# ADS7952-Q1.net
KiCad netlist of a schematic drawn in Altium Designer
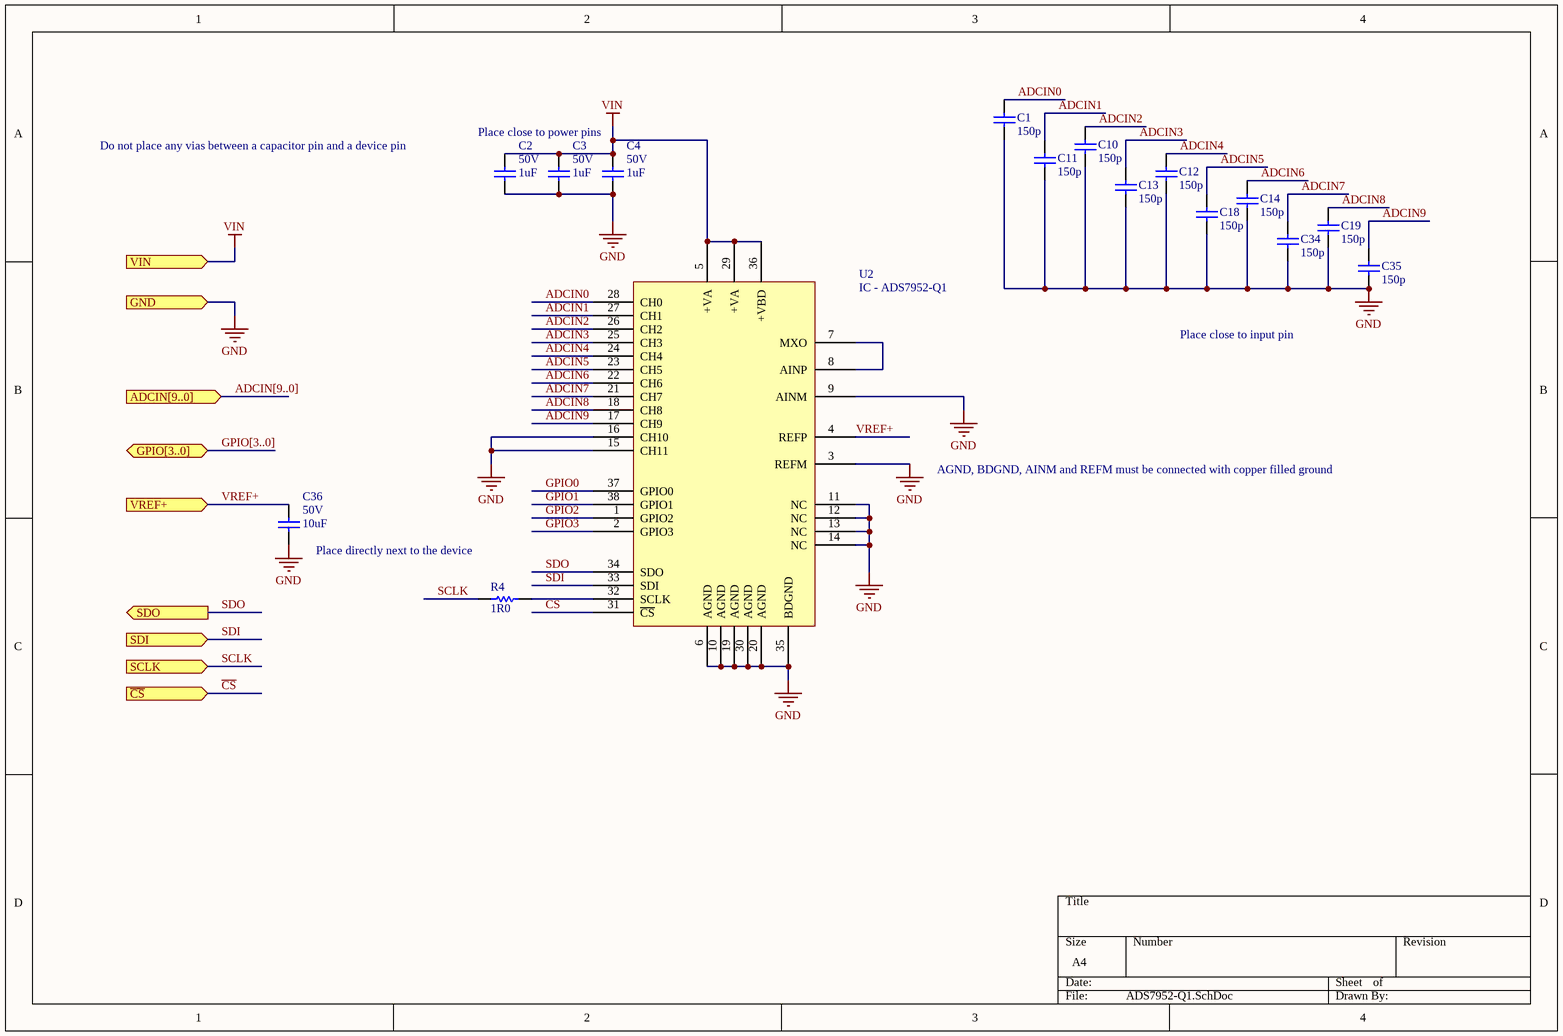
[diagram p0: ADS7952-Q1.SchDoc]

(export (version "E")
  (design (tool "Eeschema 10.0.6"))
  (components
    (comp (ref "C1")
      (value "150p")
      (footprint "CS-0603")
      (fields
        (field (name "TOLERANCE") "10%")
        (field (name "VOLTAGE") "16V")
        (field (name "Comment") "CS - CAPACITOR")
      )
      (libsource (lib "CHINOOK_LIBRARY") (part "CS - CAPACITOR"))
    )
    (comp (ref "C2")
      (value "1uF")
      (footprint "CS-0603")
      (fields
        (field (name "TOLERANCE") "10%")
        (field (name "VOLTAGE") "50V")
        (field (name "Comment") "CS - CAPACITOR")
      )
      (libsource (lib "CHINOOK_LIBRARY") (part "CS - CAPACITOR"))
    )
    (comp (ref "C3")
      (value "1uF")
      (footprint "CS-0603")
      (fields
        (field (name "TOLERANCE") "10%")
        (field (name "VOLTAGE") "50V")
        (field (name "Comment") "CS - CAPACITOR")
      )
      (libsource (lib "CHINOOK_LIBRARY") (part "CS - CAPACITOR"))
    )
    (comp (ref "C4")
      (value "1uF")
      (footprint "CS-0603")
      (fields
        (field (name "TOLERANCE") "10%")
        (field (name "VOLTAGE") "50V")
        (field (name "Comment") "CS - CAPACITOR")
      )
      (libsource (lib "CHINOOK_LIBRARY") (part "CS - CAPACITOR"))
    )
    (comp (ref "C10")
      (value "150p")
      (footprint "CS-0603")
      (fields
        (field (name "TOLERANCE") "10%")
        (field (name "VOLTAGE") "16V")
        (field (name "Comment") "CS - CAPACITOR")
      )
      (libsource (lib "CHINOOK_LIBRARY") (part "CS - CAPACITOR"))
    )
    (comp (ref "C11")
      (value "150p")
      (footprint "CS-0603")
      (fields
        (field (name "TOLERANCE") "10%")
        (field (name "VOLTAGE") "16V")
        (field (name "Comment") "CS - CAPACITOR")
      )
      (libsource (lib "CHINOOK_LIBRARY") (part "CS - CAPACITOR"))
    )
    (comp (ref "C12")
      (value "150p")
      (footprint "CS-0603")
      (fields
        (field (name "TOLERANCE") "10%")
        (field (name "VOLTAGE") "16V")
        (field (name "Comment") "CS - CAPACITOR")
      )
      (libsource (lib "CHINOOK_LIBRARY") (part "CS - CAPACITOR"))
    )
    (comp (ref "C13")
      (value "150p")
      (footprint "CS-0603")
      (fields
        (field (name "TOLERANCE") "10%")
        (field (name "VOLTAGE") "16V")
        (field (name "Comment") "CS - CAPACITOR")
      )
      (libsource (lib "CHINOOK_LIBRARY") (part "CS - CAPACITOR"))
    )
    (comp (ref "C14")
      (value "150p")
      (footprint "CS-0603")
      (fields
        (field (name "TOLERANCE") "10%")
        (field (name "VOLTAGE") "16V")
        (field (name "Comment") "CS - CAPACITOR")
      )
      (libsource (lib "CHINOOK_LIBRARY") (part "CS - CAPACITOR"))
    )
    (comp (ref "C18")
      (value "150p")
      (footprint "CS-0603")
      (fields
        (field (name "TOLERANCE") "10%")
        (field (name "VOLTAGE") "16V")
        (field (name "Comment") "CS - CAPACITOR")
      )
      (libsource (lib "CHINOOK_LIBRARY") (part "CS - CAPACITOR"))
    )
    (comp (ref "C19")
      (value "150p")
      (footprint "CS-0603")
      (fields
        (field (name "TOLERANCE") "10%")
        (field (name "VOLTAGE") "16V")
        (field (name "Comment") "CS - CAPACITOR")
      )
      (libsource (lib "CHINOOK_LIBRARY") (part "CS - CAPACITOR"))
    )
    (comp (ref "C34")
      (value "150p")
      (footprint "CS-0603")
      (fields
        (field (name "TOLERANCE") "10%")
        (field (name "VOLTAGE") "16V")
        (field (name "Comment") "CS - CAPACITOR")
      )
      (libsource (lib "CHINOOK_LIBRARY") (part "CS - CAPACITOR"))
    )
    (comp (ref "C35")
      (value "150p")
      (footprint "CS-0603")
      (fields
        (field (name "TOLERANCE") "10%")
        (field (name "VOLTAGE") "16V")
        (field (name "Comment") "CS - CAPACITOR")
      )
      (libsource (lib "CHINOOK_LIBRARY") (part "CS - CAPACITOR"))
    )
    (comp (ref "C36")
      (value "10uF")
      (footprint "CS-0603")
      (fields
        (field (name "TOLERANCE") "10%")
        (field (name "VOLTAGE") "50V")
        (field (name "Comment") "CS - CAPACITOR")
      )
      (libsource (lib "CHINOOK_LIBRARY") (part "CS - CAPACITOR"))
    )
    (comp (ref "R4")
      (value "1R0")
      (footprint "RS-0603")
      (fields
        (field (name "TOLERANCE") "RES TOL")
        (field (name "POWER") "RES POWER")
        (field (name "Comment") "RS - RESISTOR")
      )
      (libsource (lib "CHINOOK_LIBRARY") (part "RS - RESISTOR"))
    )
    (comp (ref "U2")
      (value "IC - ADS7952-Q1")
      (footprint "IC-TSSOP-38")
      (description "ADC 12 bits 12 channels MUX SPI")
      (libsource (lib "CHINOOK_LIBRARY") (part "IC - ADS7952-Q1"))
    )
  )
  (nets
    (net (code "1") (name "/ADCIN0") (class "Default")
      (node (ref "C1") (pin "2") (pinfunction "2_2") (pintype "passive"))
      (node (ref "U2") (pin "28") (pinfunction "CH0_28") (pintype "passive"))
    )
    (net (code "2") (name "/ADCIN1") (class "Default")
      (node (ref "C11") (pin "2") (pinfunction "2_2") (pintype "passive"))
      (node (ref "U2") (pin "27") (pinfunction "CH1_27") (pintype "passive"))
    )
    (net (code "3") (name "/ADCIN2") (class "Default")
      (node (ref "C10") (pin "2") (pinfunction "2_2") (pintype "passive"))
      (node (ref "U2") (pin "26") (pinfunction "CH2_26") (pintype "passive"))
    )
    (net (code "4") (name "/ADCIN3") (class "Default")
      (node (ref "C13") (pin "2") (pinfunction "2_2") (pintype "passive"))
      (node (ref "U2") (pin "25") (pinfunction "CH3_25") (pintype "passive"))
    )
    (net (code "5") (name "/ADCIN4") (class "Default")
      (node (ref "C12") (pin "2") (pinfunction "2_2") (pintype "passive"))
      (node (ref "U2") (pin "24") (pinfunction "CH4_24") (pintype "passive"))
    )
    (net (code "6") (name "/ADCIN5") (class "Default")
      (node (ref "C18") (pin "2") (pinfunction "2_2") (pintype "passive"))
      (node (ref "U2") (pin "23") (pinfunction "CH5_23") (pintype "passive"))
    )
    (net (code "7") (name "/ADCIN6") (class "Default")
      (node (ref "C14") (pin "2") (pinfunction "2_2") (pintype "passive"))
      (node (ref "U2") (pin "22") (pinfunction "CH6_22") (pintype "passive"))
    )
    (net (code "8") (name "/ADCIN7") (class "Default")
      (node (ref "C34") (pin "2") (pinfunction "2_2") (pintype "passive"))
      (node (ref "U2") (pin "21") (pinfunction "CH7_21") (pintype "passive"))
    )
    (net (code "9") (name "/ADCIN8") (class "Default")
      (node (ref "C19") (pin "2") (pinfunction "2_2") (pintype "passive"))
      (node (ref "U2") (pin "18") (pinfunction "CH8_18") (pintype "passive"))
    )
    (net (code "10") (name "/ADCIN9") (class "Default")
      (node (ref "C35") (pin "2") (pinfunction "2_2") (pintype "passive"))
      (node (ref "U2") (pin "17") (pinfunction "CH9_17") (pintype "passive"))
    )
    (net (code "12") (name "/GPIO0") (class "Default")
      (node (ref "U2") (pin "37") (pinfunction "GPIO0_37") (pintype "passive"))
    )
    (net (code "13") (name "/GPIO1") (class "Default")
      (node (ref "U2") (pin "38") (pinfunction "GPIO1_38") (pintype "passive"))
    )
    (net (code "14") (name "/GPIO2") (class "Default")
      (node (ref "U2") (pin "1") (pinfunction "GPIO2_1") (pintype "passive"))
    )
    (net (code "15") (name "/GPIO3") (class "Default")
      (node (ref "U2") (pin "2") (pinfunction "GPIO3_2") (pintype "passive"))
    )
    (net (code "17") (name "/SCLK") (class "Default")
      (node (ref "R4") (pin "2") (pinfunction "2_2") (pintype "passive"))
    )
    (net (code "18") (name "/SDI") (class "Default")
      (node (ref "U2") (pin "33") (pinfunction "SDI_33") (pintype "passive"))
    )
    (net (code "19") (name "/SDO") (class "Default")
      (node (ref "U2") (pin "34") (pinfunction "SDO_34") (pintype "passive"))
    )
    (net (code "20") (name "/VREF+") (class "Default")
      (node (ref "C36") (pin "2") (pinfunction "2_2") (pintype "passive"))
      (node (ref "U2") (pin "4") (pinfunction "REFP_4") (pintype "passive"))
    )
    (net (code "21") (name "/~{CS}") (class "Default")
      (node (ref "U2") (pin "31") (pinfunction "~{CS}_31") (pintype "passive"))
    )
    (net (code "22") (name "GND") (class "Default")
      (node (ref "C1") (pin "1") (pinfunction "1_1") (pintype "passive"))
      (node (ref "C10") (pin "1") (pinfunction "1_1") (pintype "passive"))
      (node (ref "C11") (pin "1") (pinfunction "1_1") (pintype "passive"))
      (node (ref "C12") (pin "1") (pinfunction "1_1") (pintype "passive"))
      (node (ref "C13") (pin "1") (pinfunction "1_1") (pintype "passive"))
      (node (ref "C14") (pin "1") (pinfunction "1_1") (pintype "passive"))
      (node (ref "C18") (pin "1") (pinfunction "1_1") (pintype "passive"))
      (node (ref "C19") (pin "1") (pinfunction "1_1") (pintype "passive"))
      (node (ref "C2") (pin "1") (pinfunction "1_1") (pintype "passive"))
      (node (ref "C3") (pin "1") (pinfunction "1_1") (pintype "passive"))
      (node (ref "C34") (pin "1") (pinfunction "1_1") (pintype "passive"))
      (node (ref "C35") (pin "1") (pinfunction "1_1") (pintype "passive"))
      (node (ref "C36") (pin "1") (pinfunction "1_1") (pintype "passive"))
      (node (ref "C4") (pin "1") (pinfunction "1_1") (pintype "passive"))
      (node (ref "U2") (pin "10") (pinfunction "AGND_10") (pintype "passive"))
      (node (ref "U2") (pin "11") (pinfunction "NC_11") (pintype "passive"))
      (node (ref "U2") (pin "12") (pinfunction "NC_12") (pintype "passive"))
      (node (ref "U2") (pin "13") (pinfunction "NC_13") (pintype "passive"))
      (node (ref "U2") (pin "14") (pinfunction "NC_14") (pintype "passive"))
      (node (ref "U2") (pin "15") (pinfunction "CH11_15") (pintype "passive"))
      (node (ref "U2") (pin "16") (pinfunction "CH10_16") (pintype "passive"))
      (node (ref "U2") (pin "19") (pinfunction "AGND_19") (pintype "passive"))
      (node (ref "U2") (pin "20") (pinfunction "AGND_20") (pintype "passive"))
      (node (ref "U2") (pin "3") (pinfunction "REFM_3") (pintype "passive"))
      (node (ref "U2") (pin "30") (pinfunction "AGND_30") (pintype "passive"))
      (node (ref "U2") (pin "35") (pinfunction "BDGND_35") (pintype "passive"))
      (node (ref "U2") (pin "6") (pinfunction "AGND_6") (pintype "passive"))
      (node (ref "U2") (pin "9") (pinfunction "AINM_9") (pintype "passive"))
    )
    (net (code "23") (name "Net-(U2-AINP)") (class "Default")
      (node (ref "U2") (pin "7") (pinfunction "MXO_7") (pintype "passive"))
      (node (ref "U2") (pin "8") (pinfunction "AINP_8") (pintype "passive"))
    )
    (net (code "24") (name "Net-(U2-SCLK)") (class "Default")
      (node (ref "R4") (pin "1") (pinfunction "1_1") (pintype "passive"))
      (node (ref "U2") (pin "32") (pinfunction "SCLK_32") (pintype "passive"))
    )
    (net (code "25") (name "VIN") (class "Default")
      (node (ref "C2") (pin "2") (pinfunction "2_2") (pintype "passive"))
      (node (ref "C3") (pin "2") (pinfunction "2_2") (pintype "passive"))
      (node (ref "C4") (pin "2") (pinfunction "2_2") (pintype "passive"))
      (node (ref "U2") (pin "29") (pinfunction "+VA_29") (pintype "passive"))
      (node (ref "U2") (pin "36") (pinfunction "+VBD_36") (pintype "passive"))
      (node (ref "U2") (pin "5") (pinfunction "+VA_5") (pintype "passive"))
    )
  )
)
